# lower-pcb.net
KiCad netlist of a schematic drawn in Altium Designer
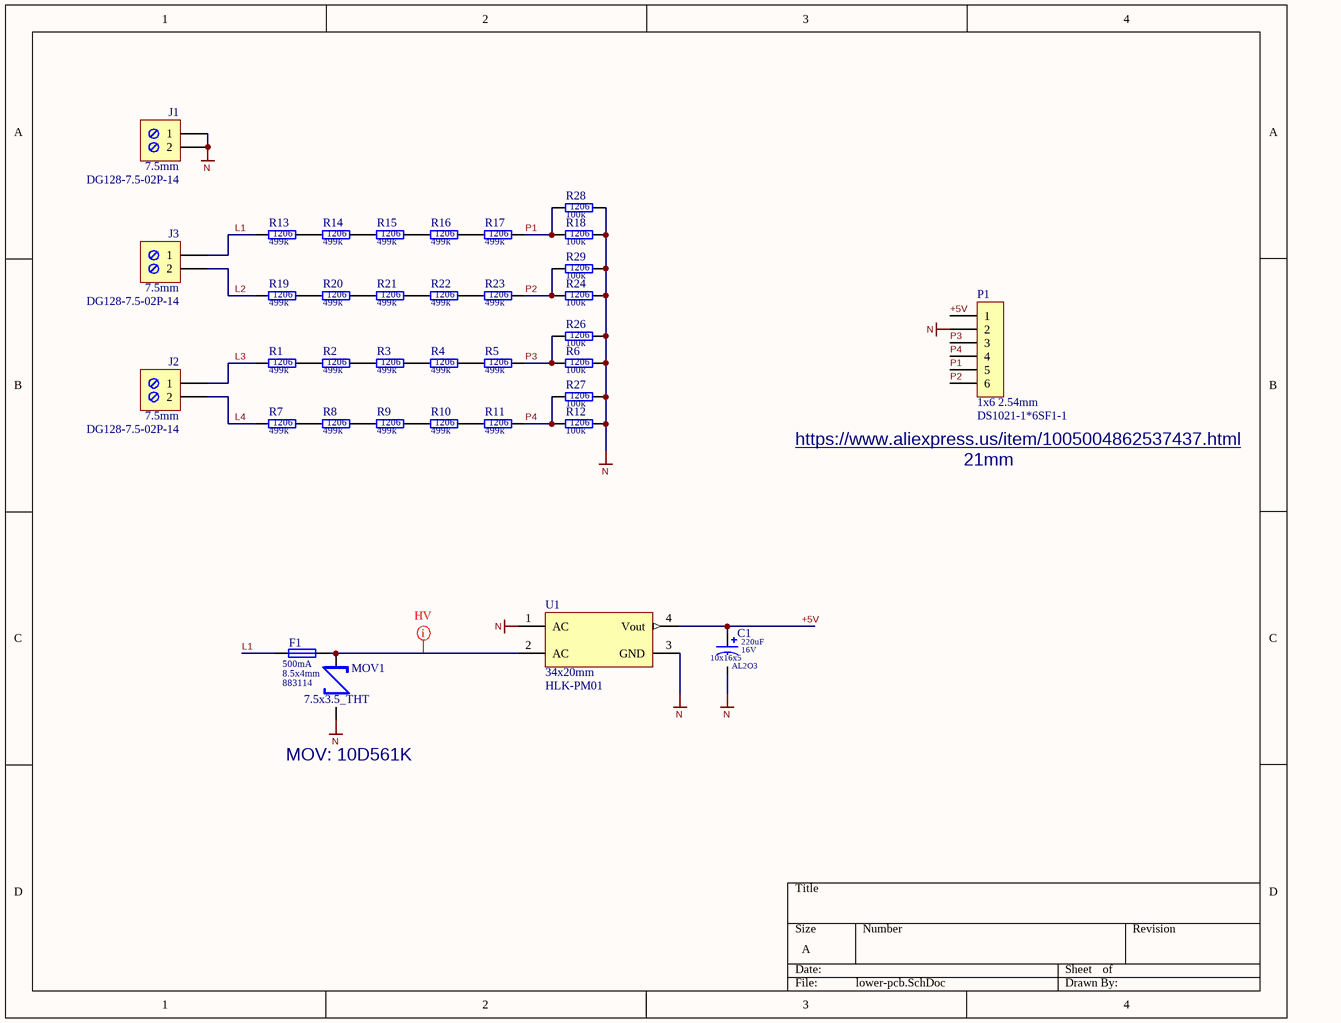
[diagram p0: lower-pcb.SchDoc]

(export (version "E")
  (design (tool "Eeschema 10.0.6"))
  (components
    (comp (ref "C1")
      (value "220uF")
      (footprint "CE_D_10x16x5_THT")
      (description "Polarized Capacitor")
      (fields
        (field (name "DIELECTRIC") "AL2O3")
        (field (name "SCH_FOOTPRINT") "10x16x5")
        (field (name "VOLTAGE") "16V")
        (field (name "PART NUMBER") "CE_680uF_16V_AL2O3_10x16x5_20")
        (field (name "MANUFACTURER") "Panasonic")
      )
      (libsource (lib "Library") (part "CE"))
    )
    (comp (ref "F1")
      (value "883114")
      (footprint "F_TE5_8.5x4")
      (description "Fuse")
      (fields
        (field (name "SCH_FOOTPRINT") "8.5x4mm")
        (field (name "CURRENT") "500mA")
        (field (name "PART NUMBER") "F_500mA_250V_TE5_8.5x4")
        (field (name "VOLTAGE") "250V")
      )
      (libsource (lib "Library") (part "F"))
    )
    (comp (ref "J1")
      (value "DG128-7.5-02P-14")
      (footprint "DG128-7.5-02P-14")
      (description "ARK Screw terminal, 2-Pin")
      (fields
        (field (name "SCH_FOOTPRINT") "7.5mm")
        (field (name "PART NUMBER") "J_DG128-7.5-02P-14")
        (field (name "MANUFACTURER") "DEGSON ELECTRONICS")
      )
      (libsource (lib "Library") (part "J_ARK2"))
    )
    (comp (ref "J2")
      (value "DG128-7.5-02P-14")
      (footprint "DG128-7.5-02P-14")
      (description "ARK Screw terminal, 2-Pin")
      (fields
        (field (name "SCH_FOOTPRINT") "7.5mm")
        (field (name "PART NUMBER") "J_DG128-7.5-02P-14")
        (field (name "MANUFACTURER") "DEGSON ELECTRONICS")
      )
      (libsource (lib "Library") (part "J_ARK2"))
    )
    (comp (ref "J3")
      (value "DG128-7.5-02P-14")
      (footprint "DG128-7.5-02P-14")
      (description "ARK Screw terminal, 2-Pin")
      (fields
        (field (name "SCH_FOOTPRINT") "7.5mm")
        (field (name "PART NUMBER") "J_DG128-7.5-02P-14")
        (field (name "MANUFACTURER") "DEGSON ELECTRONICS")
      )
      (libsource (lib "Library") (part "J_ARK2"))
    )
    (comp (ref "MOV1")
      (value "MOV")
      (footprint "MOV_AXIAL_7.5_3.5")
      (description "Varistor")
      (fields (field (name "VOLTAGE") "385VDC/300VAC") (field (name "PART NUMBER") "MOV_385VDC_300VAC_THT"))
      (libsource (lib "Library") (part "MOV"))
    )
    (comp (ref "P1")
      (value "DS1021-1*6SF1-1")
      (footprint "P_HEADER_1x6_2.54")
      (description "Pin Header")
      (fields
        (field (name "SCH_FOOTPRINT") "1x6 2.54mm")
        (field (name "PART NUMBER") "P_HEADER_1x6_2.54")
        (field (name "MANUFACTURER") "Connfly")
      )
      (libsource (lib "Library") (part "P_HEADER_1x6"))
    )
    (comp (ref "R1")
      (value "499k")
      (footprint "R_1206_3216")
      (fields
        (field (name "SCH_FOOTPRINT") "1206")
        (field (name "PART NUMBER") "R_499k_1206_1")
        (field (name "VOLTAGE") "200V")
        (field (name "POWER") "250mW")
      )
      (libsource (lib "Library") (part "R"))
    )
    (comp (ref "R2")
      (value "499k")
      (footprint "R_1206_3216")
      (fields
        (field (name "SCH_FOOTPRINT") "1206")
        (field (name "PART NUMBER") "R_499k_1206_1")
        (field (name "VOLTAGE") "200V")
        (field (name "POWER") "250mW")
      )
      (libsource (lib "Library") (part "R"))
    )
    (comp (ref "R3")
      (value "499k")
      (footprint "R_1206_3216")
      (fields
        (field (name "SCH_FOOTPRINT") "1206")
        (field (name "PART NUMBER") "R_499k_1206_1")
        (field (name "VOLTAGE") "200V")
        (field (name "POWER") "250mW")
      )
      (libsource (lib "Library") (part "R"))
    )
    (comp (ref "R4")
      (value "499k")
      (footprint "R_1206_3216")
      (fields
        (field (name "SCH_FOOTPRINT") "1206")
        (field (name "PART NUMBER") "R_499k_1206_1")
        (field (name "VOLTAGE") "200V")
        (field (name "POWER") "250mW")
      )
      (libsource (lib "Library") (part "R"))
    )
    (comp (ref "R5")
      (value "499k")
      (footprint "R_1206_3216")
      (fields
        (field (name "SCH_FOOTPRINT") "1206")
        (field (name "PART NUMBER") "R_499k_1206_1")
        (field (name "VOLTAGE") "200V")
        (field (name "POWER") "250mW")
      )
      (libsource (lib "Library") (part "R"))
    )
    (comp (ref "R6")
      (value "100k")
      (footprint "R_1206_3216")
      (fields
        (field (name "SCH_FOOTPRINT") "1206")
        (field (name "PART NUMBER") "R_100k_1206_1")
        (field (name "VOLTAGE") "200V")
        (field (name "POWER") "250mW")
      )
      (libsource (lib "Library") (part "R"))
    )
    (comp (ref "R7")
      (value "499k")
      (footprint "R_1206_3216")
      (fields
        (field (name "SCH_FOOTPRINT") "1206")
        (field (name "PART NUMBER") "R_499k_1206_1")
        (field (name "VOLTAGE") "200V")
        (field (name "POWER") "250mW")
      )
      (libsource (lib "Library") (part "R"))
    )
    (comp (ref "R8")
      (value "499k")
      (footprint "R_1206_3216")
      (fields
        (field (name "SCH_FOOTPRINT") "1206")
        (field (name "PART NUMBER") "R_499k_1206_1")
        (field (name "VOLTAGE") "200V")
        (field (name "POWER") "250mW")
      )
      (libsource (lib "Library") (part "R"))
    )
    (comp (ref "R9")
      (value "499k")
      (footprint "R_1206_3216")
      (fields
        (field (name "SCH_FOOTPRINT") "1206")
        (field (name "PART NUMBER") "R_499k_1206_1")
        (field (name "VOLTAGE") "200V")
        (field (name "POWER") "250mW")
      )
      (libsource (lib "Library") (part "R"))
    )
    (comp (ref "R10")
      (value "499k")
      (footprint "R_1206_3216")
      (fields
        (field (name "SCH_FOOTPRINT") "1206")
        (field (name "PART NUMBER") "R_499k_1206_1")
        (field (name "VOLTAGE") "200V")
        (field (name "POWER") "250mW")
      )
      (libsource (lib "Library") (part "R"))
    )
    (comp (ref "R11")
      (value "499k")
      (footprint "R_1206_3216")
      (fields
        (field (name "SCH_FOOTPRINT") "1206")
        (field (name "PART NUMBER") "R_499k_1206_1")
        (field (name "VOLTAGE") "200V")
        (field (name "POWER") "250mW")
      )
      (libsource (lib "Library") (part "R"))
    )
    (comp (ref "R12")
      (value "100k")
      (footprint "R_1206_3216")
      (fields
        (field (name "SCH_FOOTPRINT") "1206")
        (field (name "PART NUMBER") "R_100k_1206_1")
        (field (name "VOLTAGE") "200V")
        (field (name "POWER") "250mW")
      )
      (libsource (lib "Library") (part "R"))
    )
    (comp (ref "R13")
      (value "499k")
      (footprint "R_1206_3216")
      (fields
        (field (name "SCH_FOOTPRINT") "1206")
        (field (name "PART NUMBER") "R_499k_1206_1")
        (field (name "VOLTAGE") "200V")
        (field (name "POWER") "250mW")
      )
      (libsource (lib "Library") (part "R"))
    )
    (comp (ref "R14")
      (value "499k")
      (footprint "R_1206_3216")
      (fields
        (field (name "SCH_FOOTPRINT") "1206")
        (field (name "PART NUMBER") "R_499k_1206_1")
        (field (name "VOLTAGE") "200V")
        (field (name "POWER") "250mW")
      )
      (libsource (lib "Library") (part "R"))
    )
    (comp (ref "R15")
      (value "499k")
      (footprint "R_1206_3216")
      (fields
        (field (name "SCH_FOOTPRINT") "1206")
        (field (name "PART NUMBER") "R_499k_1206_1")
        (field (name "VOLTAGE") "200V")
        (field (name "POWER") "250mW")
      )
      (libsource (lib "Library") (part "R"))
    )
    (comp (ref "R16")
      (value "499k")
      (footprint "R_1206_3216")
      (fields
        (field (name "SCH_FOOTPRINT") "1206")
        (field (name "PART NUMBER") "R_499k_1206_1")
        (field (name "VOLTAGE") "200V")
        (field (name "POWER") "250mW")
      )
      (libsource (lib "Library") (part "R"))
    )
    (comp (ref "R17")
      (value "499k")
      (footprint "R_1206_3216")
      (fields
        (field (name "SCH_FOOTPRINT") "1206")
        (field (name "PART NUMBER") "R_499k_1206_1")
        (field (name "VOLTAGE") "200V")
        (field (name "POWER") "250mW")
      )
      (libsource (lib "Library") (part "R"))
    )
    (comp (ref "R18")
      (value "100k")
      (footprint "R_1206_3216")
      (fields
        (field (name "SCH_FOOTPRINT") "1206")
        (field (name "PART NUMBER") "R_100k_1206_1")
        (field (name "VOLTAGE") "200V")
        (field (name "POWER") "250mW")
      )
      (libsource (lib "Library") (part "R"))
    )
    (comp (ref "R19")
      (value "499k")
      (footprint "R_1206_3216")
      (fields
        (field (name "SCH_FOOTPRINT") "1206")
        (field (name "PART NUMBER") "R_499k_1206_1")
        (field (name "VOLTAGE") "200V")
        (field (name "POWER") "250mW")
      )
      (libsource (lib "Library") (part "R"))
    )
    (comp (ref "R20")
      (value "499k")
      (footprint "R_1206_3216")
      (fields
        (field (name "SCH_FOOTPRINT") "1206")
        (field (name "PART NUMBER") "R_499k_1206_1")
        (field (name "VOLTAGE") "200V")
        (field (name "POWER") "250mW")
      )
      (libsource (lib "Library") (part "R"))
    )
    (comp (ref "R21")
      (value "499k")
      (footprint "R_1206_3216")
      (fields
        (field (name "SCH_FOOTPRINT") "1206")
        (field (name "PART NUMBER") "R_499k_1206_1")
        (field (name "VOLTAGE") "200V")
        (field (name "POWER") "250mW")
      )
      (libsource (lib "Library") (part "R"))
    )
    (comp (ref "R22")
      (value "499k")
      (footprint "R_1206_3216")
      (fields
        (field (name "SCH_FOOTPRINT") "1206")
        (field (name "PART NUMBER") "R_499k_1206_1")
        (field (name "VOLTAGE") "200V")
        (field (name "POWER") "250mW")
      )
      (libsource (lib "Library") (part "R"))
    )
    (comp (ref "R23")
      (value "499k")
      (footprint "R_1206_3216")
      (fields
        (field (name "SCH_FOOTPRINT") "1206")
        (field (name "PART NUMBER") "R_499k_1206_1")
        (field (name "VOLTAGE") "200V")
        (field (name "POWER") "250mW")
      )
      (libsource (lib "Library") (part "R"))
    )
    (comp (ref "R24")
      (value "100k")
      (footprint "R_1206_3216")
      (fields
        (field (name "SCH_FOOTPRINT") "1206")
        (field (name "PART NUMBER") "R_100k_1206_1")
        (field (name "VOLTAGE") "200V")
        (field (name "POWER") "250mW")
      )
      (libsource (lib "Library") (part "R"))
    )
    (comp (ref "R26")
      (value "100k")
      (footprint "R_1206_3216")
      (fields
        (field (name "SCH_FOOTPRINT") "1206")
        (field (name "PART NUMBER") "R_100k_1206_1")
        (field (name "VOLTAGE") "200V")
        (field (name "POWER") "250mW")
      )
      (libsource (lib "Library") (part "R"))
    )
    (comp (ref "R27")
      (value "100k")
      (footprint "R_1206_3216")
      (fields
        (field (name "SCH_FOOTPRINT") "1206")
        (field (name "PART NUMBER") "R_100k_1206_1")
        (field (name "VOLTAGE") "200V")
        (field (name "POWER") "250mW")
      )
      (libsource (lib "Library") (part "R"))
    )
    (comp (ref "R28")
      (value "100k")
      (footprint "R_1206_3216")
      (fields
        (field (name "SCH_FOOTPRINT") "1206")
        (field (name "PART NUMBER") "R_100k_1206_1")
        (field (name "VOLTAGE") "200V")
        (field (name "POWER") "250mW")
      )
      (libsource (lib "Library") (part "R"))
    )
    (comp (ref "R29")
      (value "100k")
      (footprint "R_1206_3216")
      (fields
        (field (name "SCH_FOOTPRINT") "1206")
        (field (name "PART NUMBER") "R_100k_1206_1")
        (field (name "VOLTAGE") "200V")
        (field (name "POWER") "250mW")
      )
      (libsource (lib "Library") (part "R"))
    )
    (comp (ref "U1")
      (value "HLK-PM01")
      (footprint "VS_HLK-PMxx")
      (fields
        (field (name "SCH_FOOTPRINT") "34x20mm")
        (field (name "PART NUMBER") "VS_HLK-PM01")
        (field (name "MANUFACTURER") "Hi-Link")
        (field (name "Comment") "5V Mains power supply")
      )
      (libsource (lib "Library") (part "VS_HLK-PMxx"))
    )
  )
  (nets
    (net (code "1") (name "/+5V") (class "Default")
      (node (ref "C1") (pin "1") (pinfunction "1_1") (pintype "passive"))
      (node (ref "P1") (pin "1") (pinfunction "1_1") (pintype "passive"))
      (node (ref "U1") (pin "4") (pinfunction "Vout_4") (pintype "output"))
    )
    (net (code "2") (name "/L1") (class "Default")
      (node (ref "F1") (pin "1") (pinfunction "1_1") (pintype "passive"))
      (node (ref "J3") (pin "1") (pinfunction "1_1") (pintype "passive"))
      (node (ref "R13") (pin "1") (pinfunction "1_1") (pintype "passive"))
    )
    (net (code "3") (name "/L2") (class "Default")
      (node (ref "J3") (pin "2") (pinfunction "2_2") (pintype "passive"))
      (node (ref "R19") (pin "1") (pinfunction "1_1") (pintype "passive"))
    )
    (net (code "4") (name "/L3") (class "Default")
      (node (ref "J2") (pin "1") (pinfunction "1_1") (pintype "passive"))
      (node (ref "R1") (pin "1") (pinfunction "1_1") (pintype "passive"))
    )
    (net (code "5") (name "/L4") (class "Default")
      (node (ref "J2") (pin "2") (pinfunction "2_2") (pintype "passive"))
      (node (ref "R7") (pin "1") (pinfunction "1_1") (pintype "passive"))
    )
    (net (code "6") (name "/P1") (class "Default")
      (node (ref "P1") (pin "5") (pinfunction "5_5") (pintype "passive"))
      (node (ref "R17") (pin "2") (pinfunction "2_2") (pintype "passive"))
      (node (ref "R18") (pin "1") (pinfunction "1_1") (pintype "passive"))
      (node (ref "R28") (pin "1") (pinfunction "1_1") (pintype "passive"))
    )
    (net (code "7") (name "/P2") (class "Default")
      (node (ref "P1") (pin "6") (pinfunction "6_6") (pintype "passive"))
      (node (ref "R23") (pin "2") (pinfunction "2_2") (pintype "passive"))
      (node (ref "R24") (pin "1") (pinfunction "1_1") (pintype "passive"))
      (node (ref "R29") (pin "1") (pinfunction "1_1") (pintype "passive"))
    )
    (net (code "8") (name "/P3") (class "Default")
      (node (ref "P1") (pin "3") (pinfunction "3_3") (pintype "passive"))
      (node (ref "R26") (pin "1") (pinfunction "1_1") (pintype "passive"))
      (node (ref "R5") (pin "2") (pinfunction "2_2") (pintype "passive"))
      (node (ref "R6") (pin "1") (pinfunction "1_1") (pintype "passive"))
    )
    (net (code "9") (name "/P4") (class "Default")
      (node (ref "P1") (pin "4") (pinfunction "4_4") (pintype "passive"))
      (node (ref "R11") (pin "2") (pinfunction "2_2") (pintype "passive"))
      (node (ref "R12") (pin "1") (pinfunction "1_1") (pintype "passive"))
      (node (ref "R27") (pin "1") (pinfunction "1_1") (pintype "passive"))
    )
    (net (code "10") (name "N") (class "Default")
      (node (ref "C1") (pin "2") (pinfunction "2_2") (pintype "passive"))
      (node (ref "J1") (pin "1") (pinfunction "1_1") (pintype "passive"))
      (node (ref "J1") (pin "2") (pinfunction "2_2") (pintype "passive"))
      (node (ref "MOV1") (pin "1") (pintype "passive"))
      (node (ref "P1") (pin "2") (pinfunction "2_2") (pintype "passive"))
      (node (ref "R12") (pin "2") (pinfunction "2_2") (pintype "passive"))
      (node (ref "R18") (pin "2") (pinfunction "2_2") (pintype "passive"))
      (node (ref "R24") (pin "2") (pinfunction "2_2") (pintype "passive"))
      (node (ref "R26") (pin "2") (pinfunction "2_2") (pintype "passive"))
      (node (ref "R27") (pin "2") (pinfunction "2_2") (pintype "passive"))
      (node (ref "R28") (pin "2") (pinfunction "2_2") (pintype "passive"))
      (node (ref "R29") (pin "2") (pinfunction "2_2") (pintype "passive"))
      (node (ref "R6") (pin "2") (pinfunction "2_2") (pintype "passive"))
      (node (ref "U1") (pin "1") (pinfunction "AC_1") (pintype "power_in"))
      (node (ref "U1") (pin "3") (pinfunction "GND_3") (pintype "power_in"))
    )
    (net (code "11") (name "Net-(F1-Pad2)") (class "Default")
      (node (ref "F1") (pin "2") (pinfunction "2_2") (pintype "passive"))
      (node (ref "MOV1") (pin "2") (pintype "passive"))
      (node (ref "U1") (pin "2") (pinfunction "AC_2") (pintype "power_in"))
    )
    (net (code "12") (name "Net-(R1-Pad2)") (class "Default")
      (node (ref "R1") (pin "2") (pinfunction "2_2") (pintype "passive"))
      (node (ref "R2") (pin "1") (pinfunction "1_1") (pintype "passive"))
    )
    (net (code "13") (name "Net-(R2-Pad2)") (class "Default")
      (node (ref "R2") (pin "2") (pinfunction "2_2") (pintype "passive"))
      (node (ref "R3") (pin "1") (pinfunction "1_1") (pintype "passive"))
    )
    (net (code "14") (name "Net-(R3-Pad2)") (class "Default")
      (node (ref "R3") (pin "2") (pinfunction "2_2") (pintype "passive"))
      (node (ref "R4") (pin "1") (pinfunction "1_1") (pintype "passive"))
    )
    (net (code "15") (name "Net-(R4-Pad2)") (class "Default")
      (node (ref "R4") (pin "2") (pinfunction "2_2") (pintype "passive"))
      (node (ref "R5") (pin "1") (pinfunction "1_1") (pintype "passive"))
    )
    (net (code "16") (name "Net-(R7-Pad2)") (class "Default")
      (node (ref "R7") (pin "2") (pinfunction "2_2") (pintype "passive"))
      (node (ref "R8") (pin "1") (pinfunction "1_1") (pintype "passive"))
    )
    (net (code "17") (name "Net-(R8-Pad2)") (class "Default")
      (node (ref "R8") (pin "2") (pinfunction "2_2") (pintype "passive"))
      (node (ref "R9") (pin "1") (pinfunction "1_1") (pintype "passive"))
    )
    (net (code "18") (name "Net-(R10-Pad1)") (class "Default")
      (node (ref "R10") (pin "1") (pinfunction "1_1") (pintype "passive"))
      (node (ref "R9") (pin "2") (pinfunction "2_2") (pintype "passive"))
    )
    (net (code "19") (name "Net-(R10-Pad2)") (class "Default")
      (node (ref "R10") (pin "2") (pinfunction "2_2") (pintype "passive"))
      (node (ref "R11") (pin "1") (pinfunction "1_1") (pintype "passive"))
    )
    (net (code "20") (name "Net-(R13-Pad2)") (class "Default")
      (node (ref "R13") (pin "2") (pinfunction "2_2") (pintype "passive"))
      (node (ref "R14") (pin "1") (pinfunction "1_1") (pintype "passive"))
    )
    (net (code "21") (name "Net-(R14-Pad2)") (class "Default")
      (node (ref "R14") (pin "2") (pinfunction "2_2") (pintype "passive"))
      (node (ref "R15") (pin "1") (pinfunction "1_1") (pintype "passive"))
    )
    (net (code "22") (name "Net-(R15-Pad2)") (class "Default")
      (node (ref "R15") (pin "2") (pinfunction "2_2") (pintype "passive"))
      (node (ref "R16") (pin "1") (pinfunction "1_1") (pintype "passive"))
    )
    (net (code "23") (name "Net-(R16-Pad2)") (class "Default")
      (node (ref "R16") (pin "2") (pinfunction "2_2") (pintype "passive"))
      (node (ref "R17") (pin "1") (pinfunction "1_1") (pintype "passive"))
    )
    (net (code "24") (name "Net-(R19-Pad2)") (class "Default")
      (node (ref "R19") (pin "2") (pinfunction "2_2") (pintype "passive"))
      (node (ref "R20") (pin "1") (pinfunction "1_1") (pintype "passive"))
    )
    (net (code "25") (name "Net-(R20-Pad2)") (class "Default")
      (node (ref "R20") (pin "2") (pinfunction "2_2") (pintype "passive"))
      (node (ref "R21") (pin "1") (pinfunction "1_1") (pintype "passive"))
    )
    (net (code "26") (name "Net-(R21-Pad2)") (class "Default")
      (node (ref "R21") (pin "2") (pinfunction "2_2") (pintype "passive"))
      (node (ref "R22") (pin "1") (pinfunction "1_1") (pintype "passive"))
    )
    (net (code "27") (name "Net-(R22-Pad2)") (class "Default")
      (node (ref "R22") (pin "2") (pinfunction "2_2") (pintype "passive"))
      (node (ref "R23") (pin "1") (pinfunction "1_1") (pintype "passive"))
    )
  )
)
